# MultiDrop.net
KiCad netlist of a schematic drawn in EAGLE
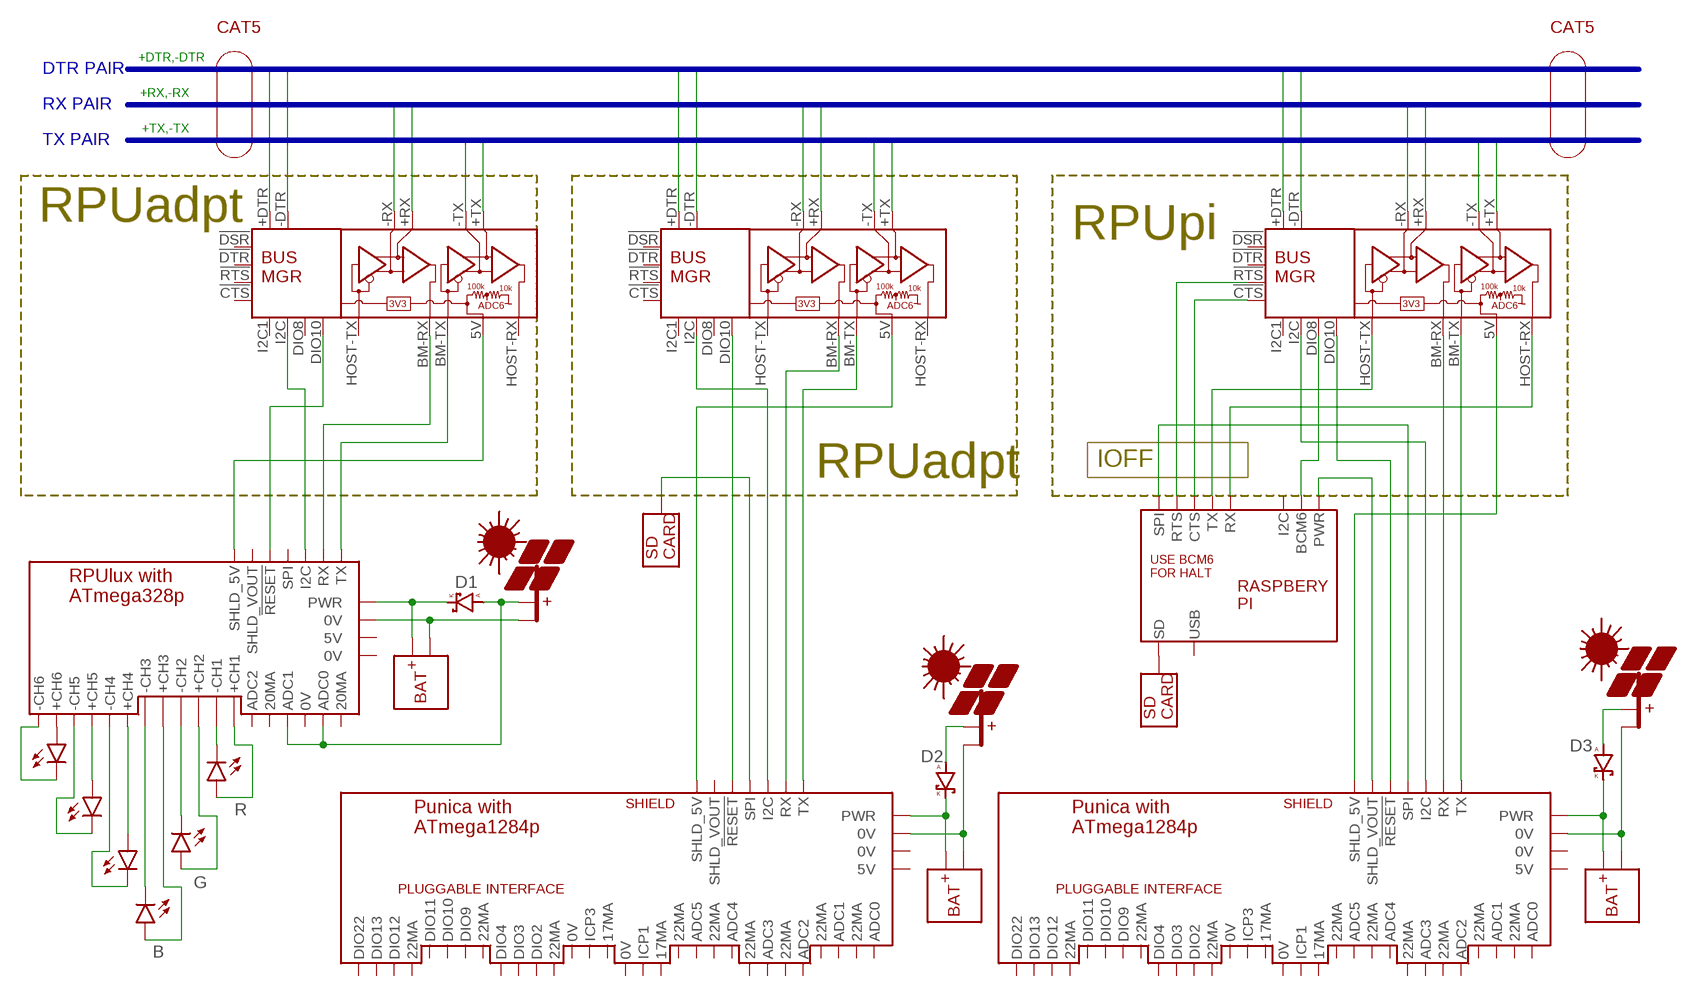
[diagram p0: schematic, sheet 1]

(export (version "E")
  (design (tool "Eeschema 10.0.6"))
  (components
    (comp (ref "B")
      (value "LED5MM")
      (footprint "eagle-import:LED5MM")
      (libsource (lib "eagle-import") (part "LED5MM"))
    )
    (comp (ref "BL2")
      (value "LED5MM")
      (footprint "eagle-import:LED5MM")
      (libsource (lib "eagle-import") (part "LED5MM"))
    )
    (comp (ref "D1")
      (value "DSMB")
      (footprint "eagle-import:SMB")
      (libsource (lib "eagle-import") (part "DSMB"))
    )
    (comp (ref "D2")
      (value "DSMB")
      (footprint "eagle-import:SMB")
      (libsource (lib "eagle-import") (part "DSMB"))
    )
    (comp (ref "D3")
      (value "DSMB")
      (footprint "eagle-import:SMB")
      (libsource (lib "eagle-import") (part "DSMB"))
    )
    (comp (ref "G")
      (value "LED5MM")
      (footprint "eagle-import:LED5MM")
      (libsource (lib "eagle-import") (part "LED5MM"))
    )
    (comp (ref "GN2")
      (value "LED5MM")
      (footprint "eagle-import:LED5MM")
      (libsource (lib "eagle-import") (part "LED5MM"))
    )
    (comp (ref "PV1")
      (value "PV")
      (footprint "eagle-import:NA-30")
      (libsource (lib "eagle-import") (part "PV"))
    )
    (comp (ref "PV2")
      (value "PV")
      (footprint "eagle-import:NA-30")
      (libsource (lib "eagle-import") (part "PV"))
    )
    (comp (ref "PV4")
      (value "PV")
      (footprint "eagle-import:NA-30")
      (libsource (lib "eagle-import") (part "PV"))
    )
    (comp (ref "R")
      (value "LED5MM")
      (footprint "eagle-import:LED5MM")
      (libsource (lib "eagle-import") (part "LED5MM"))
    )
    (comp (ref "RD2")
      (value "LED5MM")
      (footprint "eagle-import:LED5MM")
      (libsource (lib "eagle-import") (part "LED5MM"))
    )
    (comp (ref "SD1")
      (value "SD")
      (footprint "eagle-import:NA-30")
      (libsource (lib "eagle-import") (part "SD"))
    )
    (comp (ref "SD2")
      (value "SD")
      (footprint "eagle-import:NA-30")
      (libsource (lib "eagle-import") (part "SD"))
    )
    (comp (ref "U$1")
      (value "BUS_MGR")
      (footprint "eagle-import:WITH_RPU_NAMES")
      (libsource (lib "eagle-import") (part "BUS_MGR"))
    )
    (comp (ref "U$2")
      (value "BUS_MGR")
      (footprint "eagle-import:WITH_RPU_NAMES")
      (libsource (lib "eagle-import") (part "BUS_MGR"))
    )
    (comp (ref "U$3")
      (value "PI")
      (footprint "eagle-import:NA-30")
      (libsource (lib "eagle-import") (part "PI"))
    )
    (comp (ref "U$4")
      (value "BUS_MGR")
      (footprint "eagle-import:WITH_RPU_NAMES")
      (libsource (lib "eagle-import") (part "BUS_MGR"))
    )
    (comp (ref "U$5")
      (value "PUNICA")
      (footprint "eagle-import:WITH_RPU_NAMES")
      (libsource (lib "eagle-import") (part "PUNICA"))
    )
    (comp (ref "U$6")
      (value "RPULUX")
      (footprint "eagle-import:WITH_RPU_NAMES")
      (libsource (lib "eagle-import") (part "RPULUX"))
    )
    (comp (ref "U$7")
      (value "BAT")
      (footprint "eagle-import:NA-30")
      (libsource (lib "eagle-import") (part "BAT"))
    )
    (comp (ref "U$8")
      (value "PUNICA")
      (footprint "eagle-import:WITH_RPU_NAMES")
      (libsource (lib "eagle-import") (part "PUNICA"))
    )
    (comp (ref "U$9")
      (value "BAT")
      (footprint "eagle-import:NA-30")
      (libsource (lib "eagle-import") (part "BAT"))
    )
    (comp (ref "U$10")
      (value "BAT")
      (footprint "eagle-import:NA-30")
      (libsource (lib "eagle-import") (part "BAT"))
    )
  )
  (nets
    (net (code "10") (name "Net-(B-PadA)") (class "Default")
      (node (ref "B") (pin "A") (pinfunction "A_A") (pintype "passive"))
      (node (ref "U$6") (pin "+CH3") (pinfunction "+CH3_+CH3") (pintype "bidirectional"))
    )
    (net (code "11") (name "Net-(B-PadK)") (class "Default")
      (node (ref "B") (pin "K") (pinfunction "K_K") (pintype "passive"))
      (node (ref "U$6") (pin "-CH3") (pinfunction "-CH3_-CH3") (pintype "bidirectional"))
    )
    (net (code "12") (name "Net-(BL2-PadA)") (class "Default")
      (node (ref "BL2") (pin "A") (pinfunction "A_A") (pintype "passive"))
      (node (ref "U$6") (pin "+CH5") (pinfunction "+CH5_+CH5") (pintype "bidirectional"))
    )
    (net (code "13") (name "Net-(BL2-PadK)") (class "Default")
      (node (ref "BL2") (pin "K") (pinfunction "K_K") (pintype "passive"))
      (node (ref "U$6") (pin "-CH5") (pinfunction "-CH5_-CH5") (pintype "bidirectional"))
    )
    (net (code "14") (name "Net-(G-PadA)") (class "Default")
      (node (ref "G") (pin "A") (pinfunction "A_A") (pintype "passive"))
      (node (ref "U$6") (pin "+CH2") (pinfunction "+CH2_+CH2") (pintype "bidirectional"))
    )
    (net (code "15") (name "Net-(G-PadK)") (class "Default")
      (node (ref "G") (pin "K") (pinfunction "K_K") (pintype "passive"))
      (node (ref "U$6") (pin "-CH2") (pinfunction "-CH2_-CH2") (pintype "bidirectional"))
    )
    (net (code "16") (name "Net-(GN2-PadA)") (class "Default")
      (node (ref "GN2") (pin "A") (pinfunction "A_A") (pintype "passive"))
      (node (ref "U$6") (pin "+CH6") (pinfunction "+CH6_+CH6") (pintype "bidirectional"))
    )
    (net (code "17") (name "Net-(GN2-PadK)") (class "Default")
      (node (ref "GN2") (pin "K") (pinfunction "K_K") (pintype "passive"))
      (node (ref "U$6") (pin "-CH6") (pinfunction "-CH6_-CH6") (pintype "bidirectional"))
    )
    (net (code "18") (name "Net-(PV1-+PV)") (class "Default")
      (node (ref "D1") (pin "A") (pinfunction "A_A") (pintype "passive"))
      (node (ref "PV1") (pin "1") (pinfunction "+PV_1") (pintype "bidirectional"))
      (node (ref "U$6") (pin "ADC0") (pinfunction "ADC0_ADC0") (pintype "bidirectional"))
      (node (ref "U$6") (pin "ADC1") (pinfunction "ADC1_ADC1") (pintype "bidirectional"))
    )
    (net (code "19") (name "Net-(PV1--PV)") (class "Default")
      (node (ref "PV1") (pin "2") (pinfunction "-PV_2") (pintype "bidirectional"))
      (node (ref "U$10") (pin "2") (pinfunction "-BAT_2") (pintype "bidirectional"))
      (node (ref "U$6") (pin "0V@PWR") (pinfunction "0V_0V@PWR") (pintype "bidirectional"))
    )
    (net (code "20") (name "Net-(PV2-+PV)") (class "Default")
      (node (ref "D2") (pin "A") (pinfunction "A_A") (pintype "passive"))
      (node (ref "PV2") (pin "1") (pinfunction "+PV_1") (pintype "bidirectional"))
    )
    (net (code "21") (name "Net-(PV2--PV)") (class "Default")
      (node (ref "PV2") (pin "2") (pinfunction "-PV_2") (pintype "bidirectional"))
      (node (ref "U$5") (pin "0V@PWR") (pinfunction "0V_0V@PWR") (pintype "bidirectional"))
      (node (ref "U$9") (pin "2") (pinfunction "-BAT_2") (pintype "bidirectional"))
    )
    (net (code "22") (name "Net-(PV4-+PV)") (class "Default")
      (node (ref "D3") (pin "A") (pinfunction "A_A") (pintype "passive"))
      (node (ref "PV4") (pin "1") (pinfunction "+PV_1") (pintype "bidirectional"))
    )
    (net (code "23") (name "Net-(PV4--PV)") (class "Default")
      (node (ref "PV4") (pin "2") (pinfunction "-PV_2") (pintype "bidirectional"))
      (node (ref "U$7") (pin "2") (pinfunction "-BAT_2") (pintype "bidirectional"))
      (node (ref "U$8") (pin "0V@PWR") (pinfunction "0V_0V@PWR") (pintype "bidirectional"))
    )
    (net (code "24") (name "Net-(R-PadA)") (class "Default")
      (node (ref "R") (pin "A") (pinfunction "A_A") (pintype "passive"))
      (node (ref "U$6") (pin "+CH1") (pinfunction "+CH1_+CH1") (pintype "bidirectional"))
    )
    (net (code "25") (name "Net-(R-PadK)") (class "Default")
      (node (ref "R") (pin "K") (pinfunction "K_K") (pintype "passive"))
      (node (ref "U$6") (pin "-CH1") (pinfunction "-CH1_-CH1") (pintype "bidirectional"))
    )
    (net (code "26") (name "Net-(RD2-PadA)") (class "Default")
      (node (ref "RD2") (pin "A") (pinfunction "A_A") (pintype "passive"))
      (node (ref "U$6") (pin "+CH4") (pinfunction "+CH4_+CH4") (pintype "bidirectional"))
    )
    (net (code "27") (name "Net-(RD2-PadK)") (class "Default")
      (node (ref "RD2") (pin "K") (pinfunction "K_K") (pintype "passive"))
      (node (ref "U$6") (pin "-CH4") (pinfunction "-CH4_-CH4") (pintype "bidirectional"))
    )
    (net (code "28") (name "Net-(SD1-PV_PWR)") (class "Default")
      (node (ref "SD1") (pin "1") (pinfunction "PV_PWR_1") (pintype "bidirectional"))
      (node (ref "U$5") (pin "SPI") (pinfunction "SPI_SPI") (pintype "bidirectional"))
    )
    (net (code "29") (name "Net-(SD2-PV_PWR)") (class "Default")
      (node (ref "SD2") (pin "1") (pinfunction "PV_PWR_1") (pintype "bidirectional"))
      (node (ref "U$3") (pin "9") (pinfunction "SD_9") (pintype "input"))
    )
    (net (code "30") (name "Net-(U$1-BM_RX)") (class "Default")
      (node (ref "U$1") (pin "BM-RX") (pinfunction "BM_RX_BM-RX") (pintype "bidirectional"))
      (node (ref "U$8") (pin "RX") (pinfunction "RX_RX") (pintype "bidirectional"))
    )
    (net (code "31") (name "Net-(U$1-BM_TX)") (class "Default")
      (node (ref "U$1") (pin "BM-TX") (pinfunction "BM_TX_BM-TX") (pintype "bidirectional"))
      (node (ref "U$8") (pin "TX") (pinfunction "TX_TX") (pintype "bidirectional"))
    )
    (net (code "32") (name "Net-(U$1-HOST_RX)") (class "Default")
      (node (ref "U$1") (pin "HOST-RX") (pinfunction "HOST_RX_HOST-RX") (pintype "bidirectional"))
      (node (ref "U$3") (pin "3") (pinfunction "RX_3") (pintype "bidirectional"))
    )
    (net (code "33") (name "Net-(U$1-HOST_TX)") (class "Default")
      (node (ref "U$1") (pin "HOST-TX") (pinfunction "HOST_TX_HOST-TX") (pintype "bidirectional"))
      (node (ref "U$3") (pin "4") (pinfunction "TX_4") (pintype "bidirectional"))
    )
    (net (code "34") (name "Net-(U$1-PWR)") (class "Default")
      (node (ref "U$1") (pin "5V") (pinfunction "PWR_5V") (pintype "bidirectional"))
      (node (ref "U$8") (pin "SHLD_5V") (pinfunction "SHLD_5V_SHLD_5V") (pintype "bidirectional"))
    )
    (net (code "35") (name "Net-(U$1-PadI2C)") (class "Default")
      (node (ref "U$1") (pin "I2C") (pinfunction "I2C_I2C") (pintype "bidirectional"))
      (node (ref "U$8") (pin "I2C") (pinfunction "I2C_I2C") (pintype "bidirectional"))
    )
    (net (code "36") (name "Net-(U$1-~{CTS})") (class "Default")
      (node (ref "U$1") (pin "!CTS") (pinfunction "~{CTS}_!CTS") (pintype "bidirectional"))
      (node (ref "U$3") (pin "1") (pinfunction "CTS_1") (pintype "input"))
    )
    (net (code "37") (name "Net-(U$1-~{RTS})") (class "Default")
      (node (ref "U$1") (pin "!RTS") (pinfunction "~{RTS}_!RTS") (pintype "bidirectional"))
      (node (ref "U$3") (pin "2") (pinfunction "RTS_2") (pintype "input"))
    )
    (net (code "38") (name "Net-(U$2-BM_RX)") (class "Default")
      (node (ref "U$2") (pin "BM-RX") (pinfunction "BM_RX_BM-RX") (pintype "bidirectional"))
      (node (ref "U$5") (pin "RX") (pinfunction "RX_RX") (pintype "bidirectional"))
    )
    (net (code "39") (name "Net-(U$2-BM_TX)") (class "Default")
      (node (ref "U$2") (pin "BM-TX") (pinfunction "BM_TX_BM-TX") (pintype "bidirectional"))
      (node (ref "U$5") (pin "TX") (pinfunction "TX_TX") (pintype "bidirectional"))
    )
    (net (code "40") (name "Net-(U$2-PWR)") (class "Default")
      (node (ref "U$2") (pin "5V") (pinfunction "PWR_5V") (pintype "bidirectional"))
      (node (ref "U$5") (pin "SHLD_5V") (pinfunction "SHLD_5V_SHLD_5V") (pintype "bidirectional"))
    )
    (net (code "41") (name "Net-(U$2-PadI2C)") (class "Default")
      (node (ref "U$2") (pin "I2C") (pinfunction "I2C_I2C") (pintype "bidirectional"))
      (node (ref "U$5") (pin "I2C") (pinfunction "I2C_I2C") (pintype "bidirectional"))
    )
    (net (code "42") (name "Net-(U$3-BCM6)") (class "Default")
      (node (ref "U$1") (pin "DIO8") (pinfunction "DIO8_DIO8") (pintype "bidirectional"))
      (node (ref "U$3") (pin "7") (pinfunction "BCM6_7") (pintype "bidirectional"))
    )
    (net (code "43") (name "Net-(U$3-PWR)") (class "Default")
      (node (ref "U$3") (pin "12") (pinfunction "PWR_12") (pintype "bidirectional"))
      (node (ref "U$8") (pin "SHLD_VOUT") (pinfunction "SHLD_VOUT_SHLD_VOUT") (pintype "bidirectional"))
    )
    (net (code "44") (name "Net-(U$3-SPI)") (class "Default")
      (node (ref "U$3") (pin "10") (pinfunction "SPI_10") (pintype "bidirectional"))
      (node (ref "U$8") (pin "SPI") (pinfunction "SPI_SPI") (pintype "bidirectional"))
    )
    (net (code "45") (name "Net-(U$4-BM_RX)") (class "Default")
      (node (ref "U$4") (pin "BM-RX") (pinfunction "BM_RX_BM-RX") (pintype "bidirectional"))
      (node (ref "U$6") (pin "RX") (pinfunction "RX_RX") (pintype "bidirectional"))
    )
    (net (code "46") (name "Net-(U$4-BM_TX)") (class "Default")
      (node (ref "U$4") (pin "BM-TX") (pinfunction "BM_TX_BM-TX") (pintype "bidirectional"))
      (node (ref "U$6") (pin "TX") (pinfunction "TX_TX") (pintype "bidirectional"))
    )
    (net (code "47") (name "Net-(U$4-PWR)") (class "Default")
      (node (ref "U$4") (pin "5V") (pinfunction "PWR_5V") (pintype "bidirectional"))
      (node (ref "U$6") (pin "SHLD_5V") (pinfunction "SHLD_5V_SHLD_5V") (pintype "bidirectional"))
    )
    (net (code "48") (name "Net-(U$4-PadI2C)") (class "Default")
      (node (ref "U$4") (pin "I2C") (pinfunction "I2C_I2C") (pintype "bidirectional"))
      (node (ref "U$6") (pin "I2C") (pinfunction "I2C_I2C") (pintype "bidirectional"))
    )
    (net (code "49") (name "Net-(U$5-~{RESET})") (class "Default")
      (node (ref "U$2") (pin "DIO10") (pinfunction "DIO10_DIO10") (pintype "bidirectional"))
      (node (ref "U$5") (pin "!RESET") (pinfunction "~{RESET}_!RESET") (pintype "bidirectional"))
    )
    (net (code "50") (name "Net-(U$6-~{RESET})") (class "Default")
      (node (ref "U$4") (pin "DIO10") (pinfunction "DIO10_DIO10") (pintype "bidirectional"))
      (node (ref "U$6") (pin "!RESET") (pinfunction "~{RESET}_!RESET") (pintype "bidirectional"))
    )
    (net (code "51") (name "Net-(U$7-+BAT)") (class "Default")
      (node (ref "D3") (pin "K") (pinfunction "K_K") (pintype "passive"))
      (node (ref "U$7") (pin "1") (pinfunction "+BAT_1") (pintype "bidirectional"))
      (node (ref "U$8") (pin "PWR") (pinfunction "PWR_PWR") (pintype "bidirectional"))
    )
    (net (code "52") (name "Net-(U$8-~{RESET})") (class "Default")
      (node (ref "U$1") (pin "DIO10") (pinfunction "DIO10_DIO10") (pintype "bidirectional"))
      (node (ref "U$8") (pin "!RESET") (pinfunction "~{RESET}_!RESET") (pintype "bidirectional"))
    )
    (net (code "53") (name "Net-(U$9-+BAT)") (class "Default")
      (node (ref "D2") (pin "K") (pinfunction "K_K") (pintype "passive"))
      (node (ref "U$5") (pin "PWR") (pinfunction "PWR_PWR") (pintype "bidirectional"))
      (node (ref "U$9") (pin "1") (pinfunction "+BAT_1") (pintype "bidirectional"))
    )
    (net (code "54") (name "Net-(U$10-+BAT)") (class "Default")
      (node (ref "D1") (pin "K") (pinfunction "K_K") (pintype "passive"))
      (node (ref "U$10") (pin "1") (pinfunction "+BAT_1") (pintype "bidirectional"))
      (node (ref "U$6") (pin "PWR") (pinfunction "PWR_PWR") (pintype "bidirectional"))
    )
    (net (code "55") (name "unconnected-(U$1-Pad+DTR)") (class "Default")
      (node (ref "U$1") (pin "+DTR") (pinfunction "+DTR_+DTR") (pintype "bidirectional"))
    )
    (net (code "56") (name "unconnected-(U$1-Pad+RX)") (class "Default")
      (node (ref "U$1") (pin "+RX") (pinfunction "+RX_+RX") (pintype "bidirectional"))
    )
    (net (code "57") (name "unconnected-(U$1-Pad+TX)") (class "Default")
      (node (ref "U$1") (pin "+TX") (pinfunction "+TX_+TX") (pintype "bidirectional"))
    )
    (net (code "58") (name "unconnected-(U$1-Pad-DTR)") (class "Default")
      (node (ref "U$1") (pin "-DTR") (pinfunction "-DTR_-DTR") (pintype "bidirectional"))
    )
    (net (code "59") (name "unconnected-(U$1-Pad-RX)") (class "Default")
      (node (ref "U$1") (pin "-RX") (pinfunction "-RX_-RX") (pintype "bidirectional"))
    )
    (net (code "60") (name "unconnected-(U$1-Pad-TX)") (class "Default")
      (node (ref "U$1") (pin "-TX") (pinfunction "-TX_-TX") (pintype "bidirectional"))
    )
    (net (code "61") (name "unconnected-(U$1-PadI2C1)") (class "Default")
      (node (ref "U$1") (pin "I2C1") (pinfunction "I2C1_I2C1") (pintype "bidirectional"))
    )
    (net (code "62") (name "unconnected-(U$1-~{DSR}-Pad!DSR)") (class "Default")
      (node (ref "U$1") (pin "!DSR") (pinfunction "~{DSR}_!DSR") (pintype "bidirectional"))
    )
    (net (code "63") (name "unconnected-(U$1-~{DTR}-Pad!DTR)") (class "Default")
      (node (ref "U$1") (pin "!DTR") (pinfunction "~{DTR}_!DTR") (pintype "bidirectional"))
    )
    (net (code "64") (name "unconnected-(U$2-HOST_RX-PadHOST-RX)") (class "Default")
      (node (ref "U$2") (pin "HOST-RX") (pinfunction "HOST_RX_HOST-RX") (pintype "bidirectional"))
    )
    (net (code "65") (name "unconnected-(U$2-HOST_TX-PadHOST-TX)") (class "Default")
      (node (ref "U$2") (pin "HOST-TX") (pinfunction "HOST_TX_HOST-TX") (pintype "bidirectional"))
    )
    (net (code "66") (name "unconnected-(U$2-Pad+DTR)") (class "Default")
      (node (ref "U$2") (pin "+DTR") (pinfunction "+DTR_+DTR") (pintype "bidirectional"))
    )
    (net (code "67") (name "unconnected-(U$2-Pad+RX)") (class "Default")
      (node (ref "U$2") (pin "+RX") (pinfunction "+RX_+RX") (pintype "bidirectional"))
    )
    (net (code "68") (name "unconnected-(U$2-Pad+TX)") (class "Default")
      (node (ref "U$2") (pin "+TX") (pinfunction "+TX_+TX") (pintype "bidirectional"))
    )
    (net (code "69") (name "unconnected-(U$2-Pad-DTR)") (class "Default")
      (node (ref "U$2") (pin "-DTR") (pinfunction "-DTR_-DTR") (pintype "bidirectional"))
    )
    (net (code "70") (name "unconnected-(U$2-Pad-RX)") (class "Default")
      (node (ref "U$2") (pin "-RX") (pinfunction "-RX_-RX") (pintype "bidirectional"))
    )
    (net (code "71") (name "unconnected-(U$2-Pad-TX)") (class "Default")
      (node (ref "U$2") (pin "-TX") (pinfunction "-TX_-TX") (pintype "bidirectional"))
    )
    (net (code "72") (name "unconnected-(U$2-PadDIO8)") (class "Default")
      (node (ref "U$2") (pin "DIO8") (pinfunction "DIO8_DIO8") (pintype "bidirectional"))
    )
    (net (code "73") (name "unconnected-(U$2-PadI2C1)") (class "Default")
      (node (ref "U$2") (pin "I2C1") (pinfunction "I2C1_I2C1") (pintype "bidirectional"))
    )
    (net (code "74") (name "unconnected-(U$2-~{CTS}-Pad!CTS)") (class "Default")
      (node (ref "U$2") (pin "!CTS") (pinfunction "~{CTS}_!CTS") (pintype "bidirectional"))
    )
    (net (code "75") (name "unconnected-(U$2-~{DSR}-Pad!DSR)") (class "Default")
      (node (ref "U$2") (pin "!DSR") (pinfunction "~{DSR}_!DSR") (pintype "bidirectional"))
    )
    (net (code "76") (name "unconnected-(U$2-~{DTR}-Pad!DTR)") (class "Default")
      (node (ref "U$2") (pin "!DTR") (pinfunction "~{DTR}_!DTR") (pintype "bidirectional"))
    )
    (net (code "77") (name "unconnected-(U$2-~{RTS}-Pad!RTS)") (class "Default")
      (node (ref "U$2") (pin "!RTS") (pinfunction "~{RTS}_!RTS") (pintype "bidirectional"))
    )
    (net (code "78") (name "unconnected-(U$3-I2C-Pad8)") (class "Default")
      (node (ref "U$3") (pin "8") (pinfunction "I2C_8") (pintype "bidirectional"))
    )
    (net (code "79") (name "unconnected-(U$3-USB-Pad11)") (class "Default")
      (node (ref "U$3") (pin "11") (pinfunction "USB_11") (pintype "input"))
    )
    (net (code "80") (name "unconnected-(U$4-HOST_RX-PadHOST-RX)") (class "Default")
      (node (ref "U$4") (pin "HOST-RX") (pinfunction "HOST_RX_HOST-RX") (pintype "bidirectional"))
    )
    (net (code "81") (name "unconnected-(U$4-HOST_TX-PadHOST-TX)") (class "Default")
      (node (ref "U$4") (pin "HOST-TX") (pinfunction "HOST_TX_HOST-TX") (pintype "bidirectional"))
    )
    (net (code "82") (name "unconnected-(U$4-Pad+DTR)") (class "Default")
      (node (ref "U$4") (pin "+DTR") (pinfunction "+DTR_+DTR") (pintype "bidirectional"))
    )
    (net (code "83") (name "unconnected-(U$4-Pad+RX)") (class "Default")
      (node (ref "U$4") (pin "+RX") (pinfunction "+RX_+RX") (pintype "bidirectional"))
    )
    (net (code "84") (name "unconnected-(U$4-Pad+TX)") (class "Default")
      (node (ref "U$4") (pin "+TX") (pinfunction "+TX_+TX") (pintype "bidirectional"))
    )
    (net (code "85") (name "unconnected-(U$4-Pad-DTR)") (class "Default")
      (node (ref "U$4") (pin "-DTR") (pinfunction "-DTR_-DTR") (pintype "bidirectional"))
    )
    (net (code "86") (name "unconnected-(U$4-Pad-RX)") (class "Default")
      (node (ref "U$4") (pin "-RX") (pinfunction "-RX_-RX") (pintype "bidirectional"))
    )
    (net (code "87") (name "unconnected-(U$4-Pad-TX)") (class "Default")
      (node (ref "U$4") (pin "-TX") (pinfunction "-TX_-TX") (pintype "bidirectional"))
    )
    (net (code "88") (name "unconnected-(U$4-PadDIO8)") (class "Default")
      (node (ref "U$4") (pin "DIO8") (pinfunction "DIO8_DIO8") (pintype "bidirectional"))
    )
    (net (code "89") (name "unconnected-(U$4-PadI2C1)") (class "Default")
      (node (ref "U$4") (pin "I2C1") (pinfunction "I2C1_I2C1") (pintype "bidirectional"))
    )
    (net (code "90") (name "unconnected-(U$4-~{CTS}-Pad!CTS)") (class "Default")
      (node (ref "U$4") (pin "!CTS") (pinfunction "~{CTS}_!CTS") (pintype "bidirectional"))
    )
    (net (code "91") (name "unconnected-(U$4-~{DSR}-Pad!DSR)") (class "Default")
      (node (ref "U$4") (pin "!DSR") (pinfunction "~{DSR}_!DSR") (pintype "bidirectional"))
    )
    (net (code "92") (name "unconnected-(U$4-~{DTR}-Pad!DTR)") (class "Default")
      (node (ref "U$4") (pin "!DTR") (pinfunction "~{DTR}_!DTR") (pintype "bidirectional"))
    )
    (net (code "93") (name "unconnected-(U$4-~{RTS}-Pad!RTS)") (class "Default")
      (node (ref "U$4") (pin "!RTS") (pinfunction "~{RTS}_!RTS") (pintype "bidirectional"))
    )
    (net (code "94") (name "unconnected-(U$5-0V-Pad0V@ICP1)") (class "Default")
      (node (ref "U$5") (pin "0V@ICP1") (pinfunction "0V_0V@ICP1") (pintype "bidirectional"))
    )
    (net (code "95") (name "unconnected-(U$5-0V-Pad0V@ICP3)") (class "Default")
      (node (ref "U$5") (pin "0V@ICP3") (pinfunction "0V_0V@ICP3") (pintype "bidirectional"))
    )
    (net (code "96") (name "unconnected-(U$5-17MA-Pad17MA@ICP1)") (class "Default")
      (node (ref "U$5") (pin "17MA@ICP1") (pinfunction "17MA_17MA@ICP1") (pintype "bidirectional"))
    )
    (net (code "97") (name "unconnected-(U$5-17MA-Pad17MA@ICP3)") (class "Default")
      (node (ref "U$5") (pin "17MA@ICP3") (pinfunction "17MA_17MA@ICP3") (pintype "bidirectional"))
    )
    (net (code "98") (name "unconnected-(U$5-22MA-Pad22MA@ADC0)") (class "Default")
      (node (ref "U$5") (pin "22MA@ADC0") (pinfunction "22MA_22MA@ADC0") (pintype "bidirectional"))
    )
    (net (code "99") (name "unconnected-(U$5-22MA-Pad22MA@ADC1)") (class "Default")
      (node (ref "U$5") (pin "22MA@ADC1") (pinfunction "22MA_22MA@ADC1") (pintype "bidirectional"))
    )
    (net (code "100") (name "unconnected-(U$5-22MA-Pad22MA@ADC2)") (class "Default")
      (node (ref "U$5") (pin "22MA@ADC2") (pinfunction "22MA_22MA@ADC2") (pintype "bidirectional"))
    )
    (net (code "101") (name "unconnected-(U$5-22MA-Pad22MA@ADC3)") (class "Default")
      (node (ref "U$5") (pin "22MA@ADC3") (pinfunction "22MA_22MA@ADC3") (pintype "bidirectional"))
    )
    (net (code "102") (name "unconnected-(U$5-22MA-Pad22MA@ADC4)") (class "Default")
      (node (ref "U$5") (pin "22MA@ADC4") (pinfunction "22MA_22MA@ADC4") (pintype "bidirectional"))
    )
    (net (code "103") (name "unconnected-(U$5-22MA-Pad22MA@ADC5)") (class "Default")
      (node (ref "U$5") (pin "22MA@ADC5") (pinfunction "22MA_22MA@ADC5") (pintype "bidirectional"))
    )
    (net (code "104") (name "unconnected-(U$5-22MA-Pad22MA@DIO2)") (class "Default")
      (node (ref "U$5") (pin "22MA@DIO2") (pinfunction "22MA_22MA@DIO2") (pintype "bidirectional"))
    )
    (net (code "105") (name "unconnected-(U$5-22MA-Pad22MA@DIO9)") (class "Default")
      (node (ref "U$5") (pin "22MA@DIO9") (pinfunction "22MA_22MA@DIO9") (pintype "bidirectional"))
    )
    (net (code "106") (name "unconnected-(U$5-22MA-Pad22MA@DIO12)") (class "Default")
      (node (ref "U$5") (pin "22MA@DIO12") (pinfunction "22MA_22MA@DIO12") (pintype "bidirectional"))
    )
    (net (code "107") (name "unconnected-(U$5-Pad0V)") (class "Default")
      (node (ref "U$5") (pin "0V") (pinfunction "0V_0V") (pintype "bidirectional"))
    )
    (net (code "108") (name "unconnected-(U$5-Pad5V)") (class "Default")
      (node (ref "U$5") (pin "5V") (pinfunction "5V_5V") (pintype "bidirectional"))
    )
    (net (code "109") (name "unconnected-(U$5-PadADC0)") (class "Default")
      (node (ref "U$5") (pin "ADC0") (pinfunction "ADC0_ADC0") (pintype "bidirectional"))
    )
    (net (code "110") (name "unconnected-(U$5-PadADC1)") (class "Default")
      (node (ref "U$5") (pin "ADC1") (pinfunction "ADC1_ADC1") (pintype "bidirectional"))
    )
    (net (code "111") (name "unconnected-(U$5-PadADC2)") (class "Default")
      (node (ref "U$5") (pin "ADC2") (pinfunction "ADC2_ADC2") (pintype "bidirectional"))
    )
    (net (code "112") (name "unconnected-(U$5-PadADC3)") (class "Default")
      (node (ref "U$5") (pin "ADC3") (pinfunction "ADC3_ADC3") (pintype "bidirectional"))
    )
    (net (code "113") (name "unconnected-(U$5-PadADC4)") (class "Default")
      (node (ref "U$5") (pin "ADC4") (pinfunction "ADC4_ADC4") (pintype "bidirectional"))
    )
    (net (code "114") (name "unconnected-(U$5-PadADC5)") (class "Default")
      (node (ref "U$5") (pin "ADC5") (pinfunction "ADC5_ADC5") (pintype "bidirectional"))
    )
    (net (code "115") (name "unconnected-(U$5-PadDIO2)") (class "Default")
      (node (ref "U$5") (pin "DIO2") (pinfunction "DIO2_DIO2") (pintype "bidirectional"))
    )
    (net (code "116") (name "unconnected-(U$5-PadDIO3)") (class "Default")
      (node (ref "U$5") (pin "DIO3") (pinfunction "DIO3_DIO3") (pintype "bidirectional"))
    )
    (net (code "117") (name "unconnected-(U$5-PadDIO4)") (class "Default")
      (node (ref "U$5") (pin "DIO4") (pinfunction "DIO4_DIO4") (pintype "bidirectional"))
    )
    (net (code "118") (name "unconnected-(U$5-PadDIO9)") (class "Default")
      (node (ref "U$5") (pin "DIO9") (pinfunction "DIO9_DIO9") (pintype "bidirectional"))
    )
    (net (code "119") (name "unconnected-(U$5-PadDIO10)") (class "Default")
      (node (ref "U$5") (pin "DIO10") (pinfunction "DIO10_DIO10") (pintype "bidirectional"))
    )
    (net (code "120") (name "unconnected-(U$5-PadDIO11)") (class "Default")
      (node (ref "U$5") (pin "DIO11") (pinfunction "DIO11_DIO11") (pintype "bidirectional"))
    )
    (net (code "121") (name "unconnected-(U$5-PadDIO12)") (class "Default")
      (node (ref "U$5") (pin "DIO12") (pinfunction "DIO12_DIO12") (pintype "bidirectional"))
    )
    (net (code "122") (name "unconnected-(U$5-PadDIO13)") (class "Default")
      (node (ref "U$5") (pin "DIO13") (pinfunction "DIO13_DIO13") (pintype "bidirectional"))
    )
    (net (code "123") (name "unconnected-(U$5-PadDIO22)") (class "Default")
      (node (ref "U$5") (pin "DIO22") (pinfunction "DIO22_DIO22") (pintype "bidirectional"))
    )
    (net (code "124") (name "unconnected-(U$5-PadICP1)") (class "Default")
      (node (ref "U$5") (pin "ICP1") (pinfunction "ICP1_ICP1") (pintype "bidirectional"))
    )
    (net (code "125") (name "unconnected-(U$5-PadICP3)") (class "Default")
      (node (ref "U$5") (pin "ICP3") (pinfunction "ICP3_ICP3") (pintype "bidirectional"))
    )
    (net (code "126") (name "unconnected-(U$5-PadSHLD_VOUT)") (class "Default")
      (node (ref "U$5") (pin "SHLD_VOUT") (pinfunction "SHLD_VOUT_SHLD_VOUT") (pintype "bidirectional"))
    )
    (net (code "127") (name "unconnected-(U$6-0V-Pad0V@DIO2)") (class "Default")
      (node (ref "U$6") (pin "0V@DIO2") (pinfunction "0V_0V@DIO2") (pintype "bidirectional"))
    )
    (net (code "128") (name "unconnected-(U$6-20MA-Pad22MA@ADC0)") (class "Default")
      (node (ref "U$6") (pin "22MA@ADC0") (pinfunction "20MA_22MA@ADC0") (pintype "bidirectional"))
    )
    (net (code "129") (name "unconnected-(U$6-20MA-Pad22MA@ADC1)") (class "Default")
      (node (ref "U$6") (pin "22MA@ADC1") (pinfunction "20MA_22MA@ADC1") (pintype "bidirectional"))
    )
    (net (code "130") (name "unconnected-(U$6-Pad0V)") (class "Default")
      (node (ref "U$6") (pin "0V") (pinfunction "0V_0V") (pintype "bidirectional"))
    )
    (net (code "131") (name "unconnected-(U$6-Pad5V)") (class "Default")
      (node (ref "U$6") (pin "5V") (pinfunction "5V_5V") (pintype "bidirectional"))
    )
    (net (code "132") (name "unconnected-(U$6-PadADC2)") (class "Default")
      (node (ref "U$6") (pin "ADC2") (pinfunction "ADC2_ADC2") (pintype "bidirectional"))
    )
    (net (code "133") (name "unconnected-(U$6-PadSHLD_VOUT)") (class "Default")
      (node (ref "U$6") (pin "SHLD_VOUT") (pinfunction "SHLD_VOUT_SHLD_VOUT") (pintype "bidirectional"))
    )
    (net (code "134") (name "unconnected-(U$6-PadSPI)") (class "Default")
      (node (ref "U$6") (pin "SPI") (pinfunction "SPI_SPI") (pintype "bidirectional"))
    )
    (net (code "135") (name "unconnected-(U$8-0V-Pad0V@ICP1)") (class "Default")
      (node (ref "U$8") (pin "0V@ICP1") (pinfunction "0V_0V@ICP1") (pintype "bidirectional"))
    )
    (net (code "136") (name "unconnected-(U$8-0V-Pad0V@ICP3)") (class "Default")
      (node (ref "U$8") (pin "0V@ICP3") (pinfunction "0V_0V@ICP3") (pintype "bidirectional"))
    )
    (net (code "137") (name "unconnected-(U$8-17MA-Pad17MA@ICP1)") (class "Default")
      (node (ref "U$8") (pin "17MA@ICP1") (pinfunction "17MA_17MA@ICP1") (pintype "bidirectional"))
    )
    (net (code "138") (name "unconnected-(U$8-17MA-Pad17MA@ICP3)") (class "Default")
      (node (ref "U$8") (pin "17MA@ICP3") (pinfunction "17MA_17MA@ICP3") (pintype "bidirectional"))
    )
    (net (code "139") (name "unconnected-(U$8-22MA-Pad22MA@ADC0)") (class "Default")
      (node (ref "U$8") (pin "22MA@ADC0") (pinfunction "22MA_22MA@ADC0") (pintype "bidirectional"))
    )
    (net (code "140") (name "unconnected-(U$8-22MA-Pad22MA@ADC1)") (class "Default")
      (node (ref "U$8") (pin "22MA@ADC1") (pinfunction "22MA_22MA@ADC1") (pintype "bidirectional"))
    )
    (net (code "141") (name "unconnected-(U$8-22MA-Pad22MA@ADC2)") (class "Default")
      (node (ref "U$8") (pin "22MA@ADC2") (pinfunction "22MA_22MA@ADC2") (pintype "bidirectional"))
    )
    (net (code "142") (name "unconnected-(U$8-22MA-Pad22MA@ADC3)") (class "Default")
      (node (ref "U$8") (pin "22MA@ADC3") (pinfunction "22MA_22MA@ADC3") (pintype "bidirectional"))
    )
    (net (code "143") (name "unconnected-(U$8-22MA-Pad22MA@ADC4)") (class "Default")
      (node (ref "U$8") (pin "22MA@ADC4") (pinfunction "22MA_22MA@ADC4") (pintype "bidirectional"))
    )
    (net (code "144") (name "unconnected-(U$8-22MA-Pad22MA@ADC5)") (class "Default")
      (node (ref "U$8") (pin "22MA@ADC5") (pinfunction "22MA_22MA@ADC5") (pintype "bidirectional"))
    )
    (net (code "145") (name "unconnected-(U$8-22MA-Pad22MA@DIO2)") (class "Default")
      (node (ref "U$8") (pin "22MA@DIO2") (pinfunction "22MA_22MA@DIO2") (pintype "bidirectional"))
    )
    (net (code "146") (name "unconnected-(U$8-22MA-Pad22MA@DIO9)") (class "Default")
      (node (ref "U$8") (pin "22MA@DIO9") (pinfunction "22MA_22MA@DIO9") (pintype "bidirectional"))
    )
    (net (code "147") (name "unconnected-(U$8-22MA-Pad22MA@DIO12)") (class "Default")
      (node (ref "U$8") (pin "22MA@DIO12") (pinfunction "22MA_22MA@DIO12") (pintype "bidirectional"))
    )
    (net (code "148") (name "unconnected-(U$8-Pad0V)") (class "Default")
      (node (ref "U$8") (pin "0V") (pinfunction "0V_0V") (pintype "bidirectional"))
    )
    (net (code "149") (name "unconnected-(U$8-Pad5V)") (class "Default")
      (node (ref "U$8") (pin "5V") (pinfunction "5V_5V") (pintype "bidirectional"))
    )
    (net (code "150") (name "unconnected-(U$8-PadADC0)") (class "Default")
      (node (ref "U$8") (pin "ADC0") (pinfunction "ADC0_ADC0") (pintype "bidirectional"))
    )
    (net (code "151") (name "unconnected-(U$8-PadADC1)") (class "Default")
      (node (ref "U$8") (pin "ADC1") (pinfunction "ADC1_ADC1") (pintype "bidirectional"))
    )
    (net (code "152") (name "unconnected-(U$8-PadADC2)") (class "Default")
      (node (ref "U$8") (pin "ADC2") (pinfunction "ADC2_ADC2") (pintype "bidirectional"))
    )
    (net (code "153") (name "unconnected-(U$8-PadADC3)") (class "Default")
      (node (ref "U$8") (pin "ADC3") (pinfunction "ADC3_ADC3") (pintype "bidirectional"))
    )
    (net (code "154") (name "unconnected-(U$8-PadADC4)") (class "Default")
      (node (ref "U$8") (pin "ADC4") (pinfunction "ADC4_ADC4") (pintype "bidirectional"))
    )
    (net (code "155") (name "unconnected-(U$8-PadADC5)") (class "Default")
      (node (ref "U$8") (pin "ADC5") (pinfunction "ADC5_ADC5") (pintype "bidirectional"))
    )
    (net (code "156") (name "unconnected-(U$8-PadDIO2)") (class "Default")
      (node (ref "U$8") (pin "DIO2") (pinfunction "DIO2_DIO2") (pintype "bidirectional"))
    )
    (net (code "157") (name "unconnected-(U$8-PadDIO3)") (class "Default")
      (node (ref "U$8") (pin "DIO3") (pinfunction "DIO3_DIO3") (pintype "bidirectional"))
    )
    (net (code "158") (name "unconnected-(U$8-PadDIO4)") (class "Default")
      (node (ref "U$8") (pin "DIO4") (pinfunction "DIO4_DIO4") (pintype "bidirectional"))
    )
    (net (code "159") (name "unconnected-(U$8-PadDIO9)") (class "Default")
      (node (ref "U$8") (pin "DIO9") (pinfunction "DIO9_DIO9") (pintype "bidirectional"))
    )
    (net (code "160") (name "unconnected-(U$8-PadDIO10)") (class "Default")
      (node (ref "U$8") (pin "DIO10") (pinfunction "DIO10_DIO10") (pintype "bidirectional"))
    )
    (net (code "161") (name "unconnected-(U$8-PadDIO11)") (class "Default")
      (node (ref "U$8") (pin "DIO11") (pinfunction "DIO11_DIO11") (pintype "bidirectional"))
    )
    (net (code "162") (name "unconnected-(U$8-PadDIO12)") (class "Default")
      (node (ref "U$8") (pin "DIO12") (pinfunction "DIO12_DIO12") (pintype "bidirectional"))
    )
    (net (code "163") (name "unconnected-(U$8-PadDIO13)") (class "Default")
      (node (ref "U$8") (pin "DIO13") (pinfunction "DIO13_DIO13") (pintype "bidirectional"))
    )
    (net (code "164") (name "unconnected-(U$8-PadDIO22)") (class "Default")
      (node (ref "U$8") (pin "DIO22") (pinfunction "DIO22_DIO22") (pintype "bidirectional"))
    )
    (net (code "165") (name "unconnected-(U$8-PadICP1)") (class "Default")
      (node (ref "U$8") (pin "ICP1") (pinfunction "ICP1_ICP1") (pintype "bidirectional"))
    )
    (net (code "166") (name "unconnected-(U$8-PadICP3)") (class "Default")
      (node (ref "U$8") (pin "ICP3") (pinfunction "ICP3_ICP3") (pintype "bidirectional"))
    )
  )
)
